# MGMEZZ04TEST.net
KiCad netlist of a schematic drawn in Altium Designer
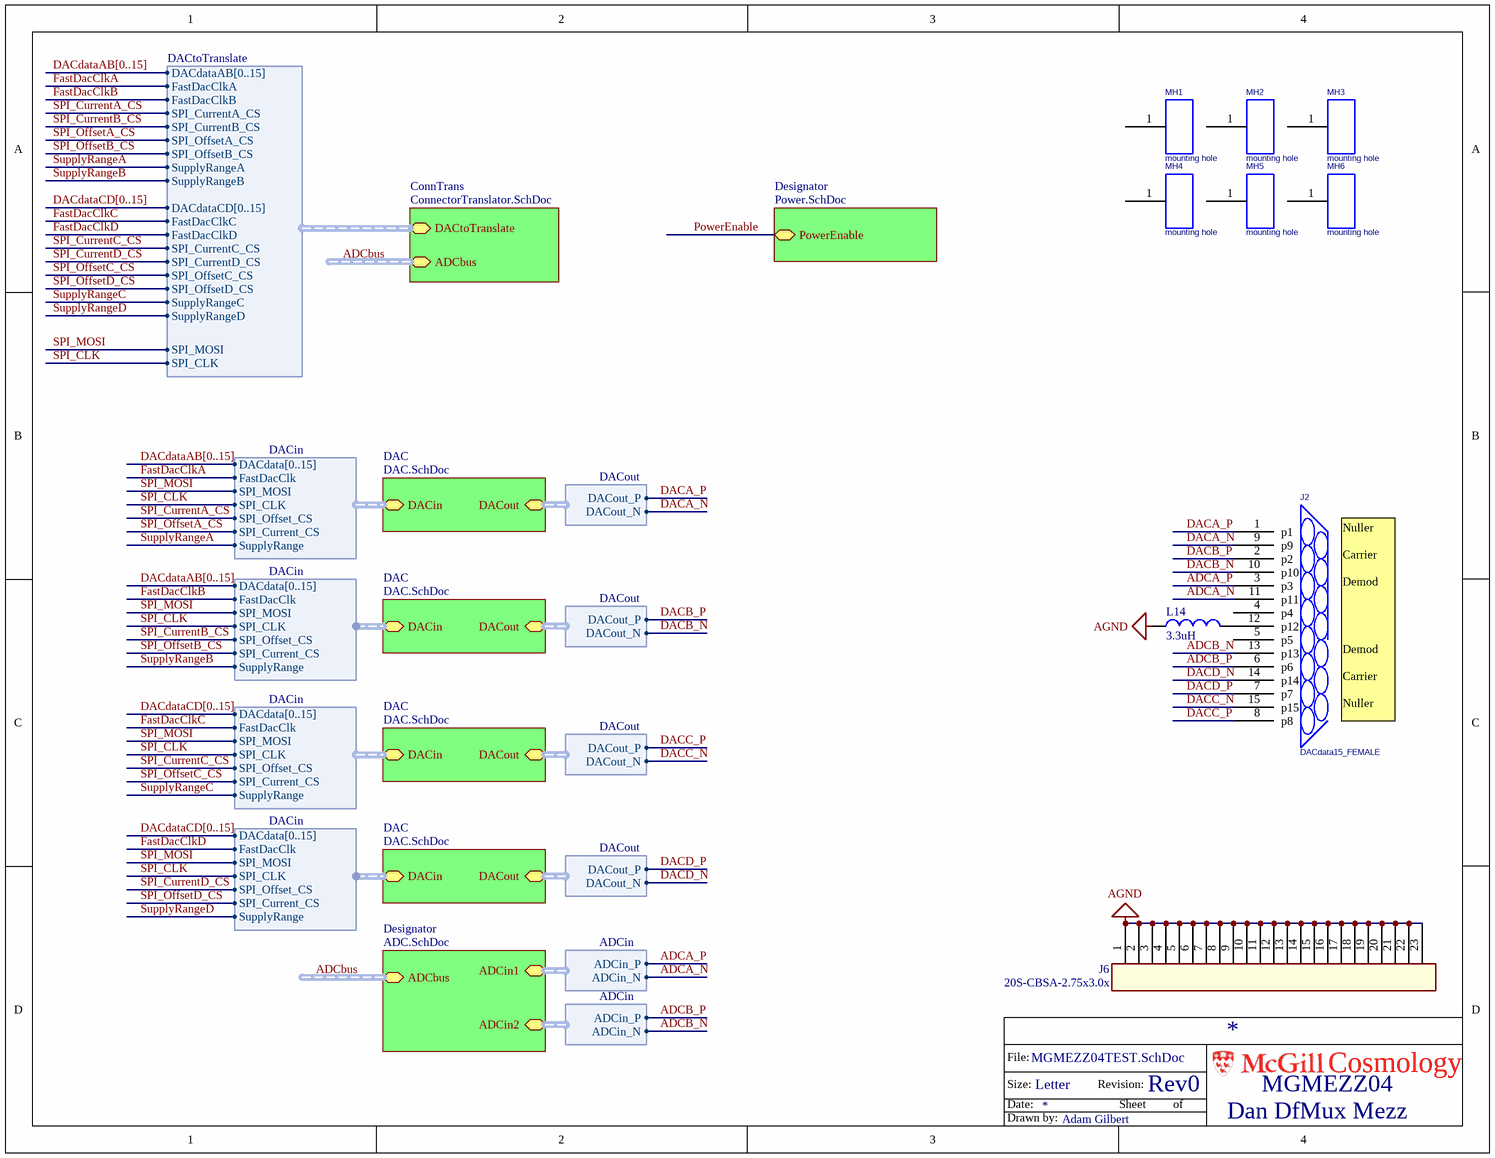
[diagram p0: MGMEZZ04TEST.SchDoc]

(export (version "E")
  (design (tool "Eeschema 10.0.6"))
  (components
    (comp (ref "J2")
      (value "DACdata15_FEMALE")
      (fields
        (field (name "MANUFACTURERS PART NUMBER") "182-015-213R181")
        (field (name "MANUFACTURER") "Norcomp")
      )
      (libsource (lib "MGMEZZ04") (part "DB15_FEMALE"))
    )
    (comp (ref "J6")
      (value "20S-CBSA-2.75x3.0x")
      (footprint "SHIELD 2.75X3.00")
      (libsource (lib "MGMEZZ04") (part "MezzShield"))
    )
    (comp (ref "L14")
      (value "3.3uH")
      (footprint "0805")
      (description "Inductor 0805")
      (fields
        (field (name "MANUFACTURER") "Coilcraft")
        (field (name "MANUFACTURERS PART NUMBER") "0805AF-332")
      )
      (libsource (lib "MGMEZZ04") (part "IND 0805"))
    )
    (comp (ref "MH1") (value "mounting hole") (libsource (lib "MGMEZZ04") (part "MTHOLE")))
    (comp (ref "MH2") (value "mounting hole") (libsource (lib "MGMEZZ04") (part "MTHOLE")))
    (comp (ref "MH3") (value "mounting hole") (libsource (lib "MGMEZZ04") (part "MTHOLE")))
    (comp (ref "MH4") (value "mounting hole") (libsource (lib "MGMEZZ04") (part "MTHOLE")))
    (comp (ref "MH5") (value "mounting hole") (libsource (lib "MGMEZZ04") (part "MTHOLE")))
    (comp (ref "MH6") (value "mounting hole") (libsource (lib "MGMEZZ04") (part "MTHOLE")))
  )
  (nets
    (net (code "37") (name "/ADCA_N") (class "Default")
      (node (ref "J2") (pin "11") (pinfunction "p11_11") (pintype "passive"))
    )
    (net (code "38") (name "/ADCA_P") (class "Default")
      (node (ref "J2") (pin "3") (pinfunction "p3_3") (pintype "passive"))
    )
    (net (code "39") (name "/ADCB_N") (class "Default")
      (node (ref "J2") (pin "13") (pinfunction "p13_13") (pintype "passive"))
    )
    (net (code "40") (name "/ADCB_P") (class "Default")
      (node (ref "J2") (pin "6") (pinfunction "p6_6") (pintype "passive"))
    )
    (net (code "41") (name "/DACA_N") (class "Default")
      (node (ref "J2") (pin "9") (pinfunction "p9_9") (pintype "passive"))
    )
    (net (code "42") (name "/DACA_P") (class "Default")
      (node (ref "J2") (pin "1") (pinfunction "p1_1") (pintype "passive"))
    )
    (net (code "43") (name "/DACB_N") (class "Default")
      (node (ref "J2") (pin "10") (pinfunction "p10_10") (pintype "passive"))
    )
    (net (code "44") (name "/DACB_P") (class "Default")
      (node (ref "J2") (pin "2") (pinfunction "p2_2") (pintype "passive"))
    )
    (net (code "45") (name "/DACC_N") (class "Default")
      (node (ref "J2") (pin "15") (pinfunction "p15_15") (pintype "passive"))
    )
    (net (code "46") (name "/DACC_P") (class "Default")
      (node (ref "J2") (pin "8") (pinfunction "p8_8") (pintype "passive"))
    )
    (net (code "47") (name "/DACD_N") (class "Default")
      (node (ref "J2") (pin "14") (pinfunction "p14_14") (pintype "passive"))
    )
    (net (code "48") (name "/DACD_P") (class "Default")
      (node (ref "J2") (pin "7") (pinfunction "p7_7") (pintype "passive"))
    )
    (net (code "76") (name "AGND") (class "Default")
      (node (ref "J6") (pin "1") (pinfunction "1_1") (pintype "passive"))
      (node (ref "J6") (pin "10") (pinfunction "10_10") (pintype "passive"))
      (node (ref "J6") (pin "11") (pinfunction "11_11") (pintype "passive"))
      (node (ref "J6") (pin "12") (pinfunction "12_12") (pintype "passive"))
      (node (ref "J6") (pin "13") (pinfunction "13_13") (pintype "passive"))
      (node (ref "J6") (pin "14") (pinfunction "14_14") (pintype "passive"))
      (node (ref "J6") (pin "15") (pinfunction "15_15") (pintype "passive"))
      (node (ref "J6") (pin "16") (pinfunction "16_16") (pintype "passive"))
      (node (ref "J6") (pin "17") (pinfunction "17_17") (pintype "passive"))
      (node (ref "J6") (pin "18") (pinfunction "18_18") (pintype "passive"))
      (node (ref "J6") (pin "19") (pinfunction "19_19") (pintype "passive"))
      (node (ref "J6") (pin "2") (pinfunction "2_2") (pintype "passive"))
      (node (ref "J6") (pin "20") (pinfunction "20_20") (pintype "passive"))
      (node (ref "J6") (pin "21") (pinfunction "21_21") (pintype "passive"))
      (node (ref "J6") (pin "22") (pinfunction "22_22") (pintype "passive"))
      (node (ref "J6") (pin "23") (pinfunction "23_23") (pintype "passive"))
      (node (ref "J6") (pin "3") (pinfunction "3_3") (pintype "passive"))
      (node (ref "J6") (pin "4") (pinfunction "4_4") (pintype "passive"))
      (node (ref "J6") (pin "5") (pinfunction "5_5") (pintype "passive"))
      (node (ref "J6") (pin "6") (pinfunction "6_6") (pintype "passive"))
      (node (ref "J6") (pin "7") (pinfunction "7_7") (pintype "passive"))
      (node (ref "J6") (pin "8") (pinfunction "8_8") (pintype "passive"))
      (node (ref "J6") (pin "9") (pinfunction "9_9") (pintype "passive"))
      (node (ref "L14") (pin "1") (pinfunction "1_1") (pintype "passive"))
    )
    (net (code "77") (name "Net-(J2-p12)") (class "Default")
      (node (ref "J2") (pin "12") (pinfunction "p12_12") (pintype "passive"))
      (node (ref "L14") (pin "2") (pinfunction "2_2") (pintype "passive"))
    )
    (net (code "78") (name "unconnected-(J2-p4-Pad4)") (class "Default")
      (node (ref "J2") (pin "4") (pinfunction "p4_4") (pintype "passive"))
    )
    (net (code "79") (name "unconnected-(J2-p5-Pad5)") (class "Default")
      (node (ref "J2") (pin "5") (pinfunction "p5_5") (pintype "passive"))
    )
    (net (code "80") (name "unconnected-(MH1-A-Pad1)") (class "Default")
      (node (ref "MH1") (pin "1") (pinfunction "A_1") (pintype "passive"))
    )
    (net (code "81") (name "unconnected-(MH2-A-Pad1)") (class "Default")
      (node (ref "MH2") (pin "1") (pinfunction "A_1") (pintype "passive"))
    )
    (net (code "82") (name "unconnected-(MH3-A-Pad1)") (class "Default")
      (node (ref "MH3") (pin "1") (pinfunction "A_1") (pintype "passive"))
    )
    (net (code "83") (name "unconnected-(MH4-A-Pad1)") (class "Default")
      (node (ref "MH4") (pin "1") (pinfunction "A_1") (pintype "passive"))
    )
    (net (code "84") (name "unconnected-(MH5-A-Pad1)") (class "Default")
      (node (ref "MH5") (pin "1") (pinfunction "A_1") (pintype "passive"))
    )
    (net (code "85") (name "unconnected-(MH6-A-Pad1)") (class "Default")
      (node (ref "MH6") (pin "1") (pinfunction "A_1") (pintype "passive"))
    )
  )
)
